# gamebuino-hack.net
KiCad netlist of a schematic drawn in EAGLE
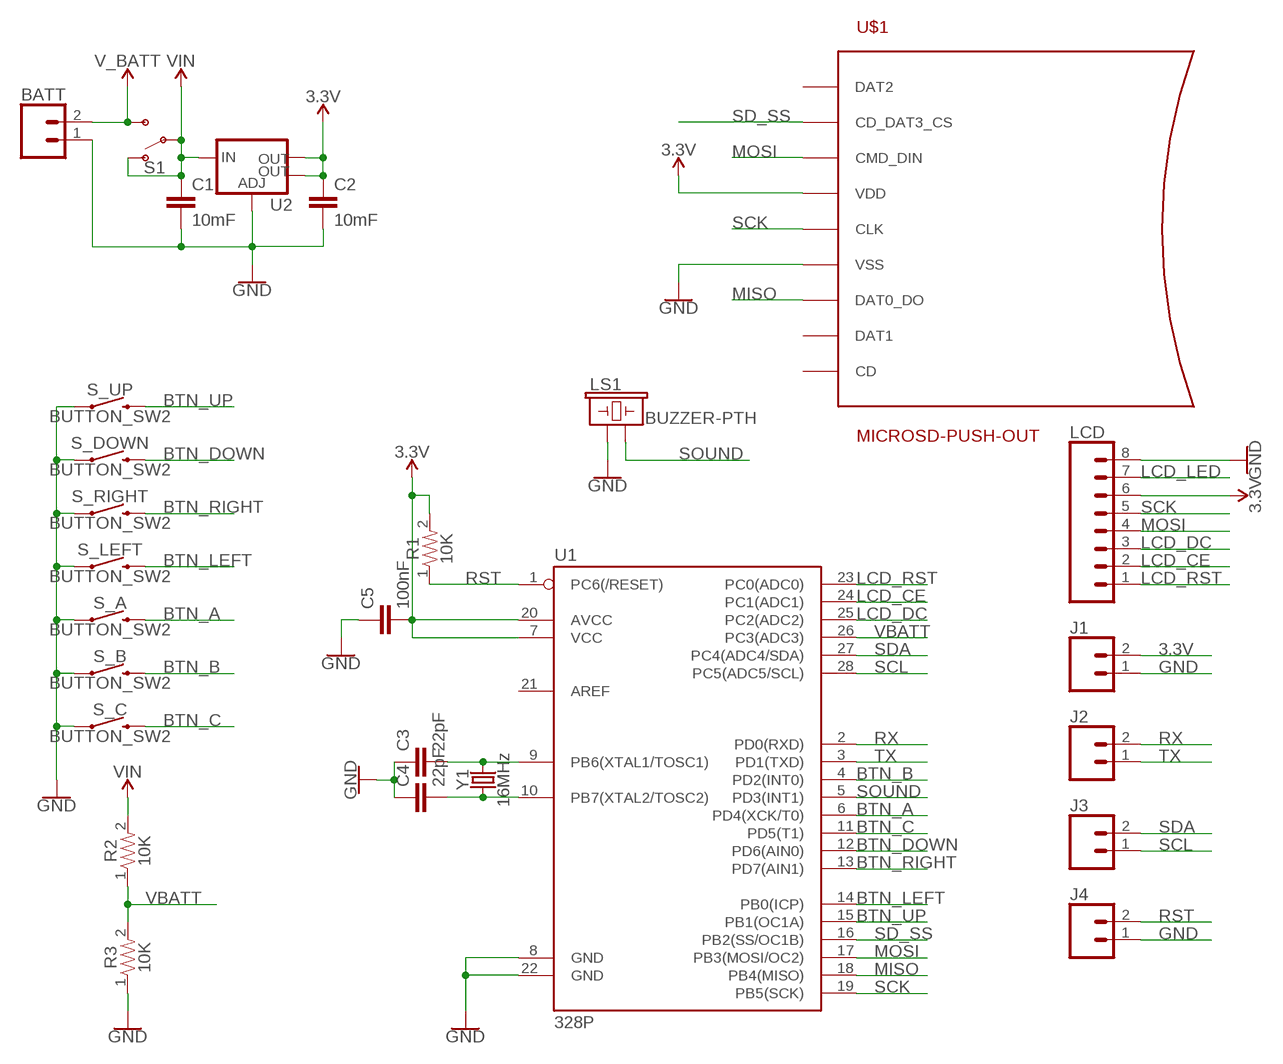
[diagram p0: schematic, sheet 1]

(export (version "E")
  (design (tool "Eeschema 10.0.6"))
  (components
    (comp (ref "BATT")
      (value "CONN_02")
      (footprint "eagle-import:1X02")
      (libsource (lib "eagle-import") (part "CONN_02"))
    )
    (comp (ref "C1")
      (value "10mF")
      (footprint "eagle-import:0805")
      (libsource (lib "eagle-import") (part "CAP-805"))
    )
    (comp (ref "C2")
      (value "10mF")
      (footprint "eagle-import:0805")
      (libsource (lib "eagle-import") (part "CAP-805"))
    )
    (comp (ref "C3")
      (value "22pF")
      (footprint "eagle-import:0805")
      (libsource (lib "eagle-import") (part "CAP-805"))
    )
    (comp (ref "C4")
      (value "22pF")
      (footprint "eagle-import:0805")
      (libsource (lib "eagle-import") (part "CAP-805"))
    )
    (comp (ref "C5")
      (value "100nF")
      (footprint "eagle-import:0805")
      (libsource (lib "eagle-import") (part "CAP-805"))
    )
    (comp (ref "J1")
      (value "CONN_02")
      (footprint "eagle-import:1X02")
      (libsource (lib "eagle-import") (part "CONN_02"))
    )
    (comp (ref "J2")
      (value "CONN_02")
      (footprint "eagle-import:1X02")
      (libsource (lib "eagle-import") (part "CONN_02"))
    )
    (comp (ref "J3")
      (value "CONN_02")
      (footprint "eagle-import:1X02")
      (libsource (lib "eagle-import") (part "CONN_02"))
    )
    (comp (ref "J4")
      (value "CONN_02")
      (footprint "eagle-import:1X02")
      (libsource (lib "eagle-import") (part "CONN_02"))
    )
    (comp (ref "LCD")
      (value "CONN_08\"")
      (footprint "eagle-import:1X08")
      (libsource (lib "eagle-import") (part "CONN_08{dblquote}"))
    )
    (comp (ref "LS1")
      (value "BUZZER-PTH")
      (footprint "eagle-import:BUZZER-12MM")
      (libsource (lib "eagle-import") (part "BUZZER-PTH"))
    )
    (comp (ref "R1")
      (value "10K")
      (footprint "eagle-import:0805")
      (libsource (lib "eagle-import") (part "RESISTOR-805"))
    )
    (comp (ref "R2")
      (value "10K")
      (footprint "eagle-import:0805")
      (libsource (lib "eagle-import") (part "RESISTOR-805"))
    )
    (comp (ref "R3")
      (value "10K")
      (footprint "eagle-import:0805")
      (libsource (lib "eagle-import") (part "RESISTOR-805"))
    )
    (comp (ref "S1")
      (value "SWITCH-SPDT-PTH-11.6X4.0MM")
      (footprint "eagle-import:SWITCH_SPDT_PTH_11.6X4.0MM")
      (libsource (lib "eagle-import") (part "SWITCH-SPDT-PTH-11.6X4.0MM"))
    )
    (comp (ref "S_A")
      (value "BUTTON_SW2")
      (footprint "eagle-import:BUTTON_SW2")
      (libsource (lib "eagle-import") (part "BUTTON_SW2"))
    )
    (comp (ref "S_B")
      (value "BUTTON_SW2")
      (footprint "eagle-import:BUTTON_SW2")
      (libsource (lib "eagle-import") (part "BUTTON_SW2"))
    )
    (comp (ref "S_C")
      (value "BUTTON_SW2")
      (footprint "eagle-import:BUTTON_SW2")
      (libsource (lib "eagle-import") (part "BUTTON_SW2"))
    )
    (comp (ref "S_DOWN")
      (value "BUTTON_SW2")
      (footprint "eagle-import:BUTTON_SW2")
      (libsource (lib "eagle-import") (part "BUTTON_SW2"))
    )
    (comp (ref "S_LEFT")
      (value "BUTTON_SW2")
      (footprint "eagle-import:BUTTON_SW2")
      (libsource (lib "eagle-import") (part "BUTTON_SW2"))
    )
    (comp (ref "S_RIGHT")
      (value "BUTTON_SW2")
      (footprint "eagle-import:BUTTON_SW2")
      (libsource (lib "eagle-import") (part "BUTTON_SW2"))
    )
    (comp (ref "S_UP")
      (value "BUTTON_SW2")
      (footprint "eagle-import:BUTTON_SW2")
      (libsource (lib "eagle-import") (part "BUTTON_SW2"))
    )
    (comp (ref "U$1")
      (value "MICROSD-PUSH-OUT")
      (footprint "eagle-import:MICROSD-PUSH-OUT")
      (libsource (lib "eagle-import") (part "MICROSD-PUSH-OUT"))
    )
    (comp (ref "U1")
      (value "328P")
      (footprint "eagle-import:DIP28")
      (libsource (lib "eagle-import") (part "ATMEGA328P_PDIP"))
    )
    (comp (ref "U2")
      (value "V_REG_LM1117SOT223")
      (footprint "eagle-import:SOT223")
      (libsource (lib "eagle-import") (part "V_REG_LM1117SOT223"))
    )
    (comp (ref "Y1")
      (value "16MHz")
      (footprint "eagle-import:HC49US")
      (libsource (lib "eagle-import") (part "CRYSTAL-16MHZPTH-HC49US"))
    )
  )
  (nets
    (net (code "1") (name "/BTN_A") (class "Default")
      (node (ref "S_A") (pin "2") (pinfunction "2_2") (pintype "passive"))
      (node (ref "U1") (pin "6") (pinfunction "PD4(XCK/T0)_6") (pintype "bidirectional"))
    )
    (net (code "2") (name "/BTN_B") (class "Default")
      (node (ref "S_B") (pin "2") (pinfunction "2_2") (pintype "passive"))
      (node (ref "U1") (pin "4") (pinfunction "PD2(INT0)_4") (pintype "bidirectional"))
    )
    (net (code "3") (name "/BTN_C") (class "Default")
      (node (ref "S_C") (pin "2") (pinfunction "2_2") (pintype "passive"))
      (node (ref "U1") (pin "11") (pinfunction "PD5(T1)_11") (pintype "bidirectional"))
    )
    (net (code "4") (name "/BTN_DOWN") (class "Default")
      (node (ref "S_DOWN") (pin "2") (pinfunction "2_2") (pintype "passive"))
      (node (ref "U1") (pin "12") (pinfunction "PD6(AIN0)_12") (pintype "bidirectional"))
    )
    (net (code "5") (name "/BTN_LEFT") (class "Default")
      (node (ref "S_LEFT") (pin "2") (pinfunction "2_2") (pintype "passive"))
      (node (ref "U1") (pin "14") (pinfunction "PB0(ICP)_14") (pintype "bidirectional"))
    )
    (net (code "6") (name "/BTN_RIGHT") (class "Default")
      (node (ref "S_RIGHT") (pin "2") (pinfunction "2_2") (pintype "passive"))
      (node (ref "U1") (pin "13") (pinfunction "PD7(AIN1)_13") (pintype "bidirectional"))
    )
    (net (code "7") (name "/BTN_UP") (class "Default")
      (node (ref "S_UP") (pin "2") (pinfunction "2_2") (pintype "passive"))
      (node (ref "U1") (pin "15") (pinfunction "PB1(OC1A)_15") (pintype "bidirectional"))
    )
    (net (code "8") (name "/LCD_CE") (class "Default")
      (node (ref "LCD") (pin "2") (pinfunction "2_2") (pintype "passive"))
      (node (ref "U1") (pin "24") (pinfunction "PC1(ADC1)_24") (pintype "bidirectional"))
    )
    (net (code "9") (name "/LCD_DC") (class "Default")
      (node (ref "LCD") (pin "3") (pinfunction "3_3") (pintype "passive"))
      (node (ref "U1") (pin "25") (pinfunction "PC2(ADC2)_25") (pintype "bidirectional"))
    )
    (net (code "10") (name "/LCD_LED") (class "Default")
      (node (ref "LCD") (pin "7") (pinfunction "7_7") (pintype "passive"))
    )
    (net (code "11") (name "/LCD_RST") (class "Default")
      (node (ref "LCD") (pin "1") (pinfunction "1_1") (pintype "passive"))
      (node (ref "U1") (pin "23") (pinfunction "PC0(ADC0)_23") (pintype "bidirectional"))
    )
    (net (code "12") (name "/MISO") (class "Default")
      (node (ref "U$1") (pin "7") (pinfunction "DAT0_DO_7") (pintype "bidirectional"))
      (node (ref "U1") (pin "18") (pinfunction "PB4(MISO)_18") (pintype "bidirectional"))
    )
    (net (code "13") (name "/MOSI") (class "Default")
      (node (ref "LCD") (pin "4") (pinfunction "4_4") (pintype "passive"))
      (node (ref "U$1") (pin "3") (pinfunction "CMD_DIN_3") (pintype "bidirectional"))
      (node (ref "U1") (pin "17") (pinfunction "PB3(MOSI/OC2)_17") (pintype "bidirectional"))
    )
    (net (code "14") (name "/RST") (class "Default")
      (node (ref "J4") (pin "2") (pinfunction "2_2") (pintype "passive"))
      (node (ref "R1") (pin "1") (pinfunction "1_1") (pintype "passive"))
      (node (ref "U1") (pin "1") (pinfunction "PC6(/RESET)_1") (pintype "bidirectional"))
    )
    (net (code "15") (name "/RX") (class "Default")
      (node (ref "J2") (pin "2") (pinfunction "2_2") (pintype "passive"))
      (node (ref "U1") (pin "2") (pinfunction "PD0(RXD)_2") (pintype "bidirectional"))
    )
    (net (code "16") (name "/SCK") (class "Default")
      (node (ref "LCD") (pin "5") (pinfunction "5_5") (pintype "passive"))
      (node (ref "U$1") (pin "5") (pinfunction "CLK_5") (pintype "bidirectional"))
      (node (ref "U1") (pin "19") (pinfunction "PB5(SCK)_19") (pintype "bidirectional"))
    )
    (net (code "17") (name "/SCL") (class "Default")
      (node (ref "J3") (pin "1") (pinfunction "1_1") (pintype "passive"))
      (node (ref "U1") (pin "28") (pinfunction "PC5(ADC5/SCL)_28") (pintype "bidirectional"))
    )
    (net (code "18") (name "/SDA") (class "Default")
      (node (ref "J3") (pin "2") (pinfunction "2_2") (pintype "passive"))
      (node (ref "U1") (pin "27") (pinfunction "PC4(ADC4/SDA)_27") (pintype "bidirectional"))
    )
    (net (code "19") (name "/SD_SS") (class "Default")
      (node (ref "U$1") (pin "2") (pinfunction "CD_DAT3_CS_2") (pintype "bidirectional"))
      (node (ref "U1") (pin "16") (pinfunction "PB2(SS/OC1B)_16") (pintype "bidirectional"))
    )
    (net (code "20") (name "/SOUND") (class "Default")
      (node (ref "LS1") (pin "-") (pinfunction "2_-") (pintype "passive"))
      (node (ref "U1") (pin "5") (pinfunction "PD3(INT1)_5") (pintype "bidirectional"))
    )
    (net (code "21") (name "/TX") (class "Default")
      (node (ref "J2") (pin "1") (pinfunction "1_1") (pintype "passive"))
      (node (ref "U1") (pin "3") (pinfunction "PD1(TXD)_3") (pintype "bidirectional"))
    )
    (net (code "22") (name "/VBATT") (class "Default")
      (node (ref "R2") (pin "1") (pinfunction "1_1") (pintype "passive"))
      (node (ref "R3") (pin "2") (pinfunction "2_2") (pintype "passive"))
      (node (ref "U1") (pin "26") (pinfunction "PC3(ADC3)_26") (pintype "bidirectional"))
    )
    (net (code "23") (name "3.3V") (class "Default")
      (node (ref "C2") (pin "1") (pinfunction "1_1") (pintype "passive"))
      (node (ref "C5") (pin "2") (pinfunction "2_2") (pintype "passive"))
      (node (ref "J1") (pin "2") (pinfunction "2_2") (pintype "passive"))
      (node (ref "LCD") (pin "6") (pinfunction "6_6") (pintype "passive"))
      (node (ref "R1") (pin "2") (pinfunction "2_2") (pintype "passive"))
      (node (ref "U$1") (pin "4") (pinfunction "VDD_4") (pintype "bidirectional"))
      (node (ref "U1") (pin "20") (pinfunction "AVCC_20") (pintype "bidirectional"))
      (node (ref "U1") (pin "7") (pinfunction "VCC_7") (pintype "bidirectional"))
      (node (ref "U2") (pin "2") (pinfunction "OUT_2") (pintype "output"))
      (node (ref "U2") (pin "4") (pinfunction "OUT_4") (pintype "output"))
    )
    (net (code "24") (name "GND") (class "Default")
      (node (ref "BATT") (pin "1") (pinfunction "1_1") (pintype "passive"))
      (node (ref "C1") (pin "2") (pinfunction "2_2") (pintype "passive"))
      (node (ref "C2") (pin "2") (pinfunction "2_2") (pintype "passive"))
      (node (ref "C3") (pin "1") (pinfunction "1_1") (pintype "passive"))
      (node (ref "C4") (pin "1") (pinfunction "1_1") (pintype "passive"))
      (node (ref "C5") (pin "1") (pinfunction "1_1") (pintype "passive"))
      (node (ref "J1") (pin "1") (pinfunction "1_1") (pintype "passive"))
      (node (ref "J4") (pin "1") (pinfunction "1_1") (pintype "passive"))
      (node (ref "LCD") (pin "8") (pinfunction "8_8") (pintype "passive"))
      (node (ref "LS1") (pin "+") (pinfunction "1_+") (pintype "passive"))
      (node (ref "R3") (pin "1") (pinfunction "1_1") (pintype "passive"))
      (node (ref "S_A") (pin "1") (pinfunction "1_1") (pintype "passive"))
      (node (ref "S_B") (pin "1") (pinfunction "1_1") (pintype "passive"))
      (node (ref "S_C") (pin "1") (pinfunction "1_1") (pintype "passive"))
      (node (ref "S_DOWN") (pin "1") (pinfunction "1_1") (pintype "passive"))
      (node (ref "S_LEFT") (pin "1") (pinfunction "1_1") (pintype "passive"))
      (node (ref "S_RIGHT") (pin "1") (pinfunction "1_1") (pintype "passive"))
      (node (ref "S_UP") (pin "1") (pinfunction "1_1") (pintype "passive"))
      (node (ref "U$1") (pin "6") (pinfunction "VSS_6") (pintype "bidirectional"))
      (node (ref "U$1") (pin "G1") (pinfunction "VSS_G1") (pintype "bidirectional"))
      (node (ref "U$1") (pin "G2") (pinfunction "VSS_G2") (pintype "bidirectional"))
      (node (ref "U$1") (pin "G3") (pinfunction "VSS_G3") (pintype "bidirectional"))
      (node (ref "U$1") (pin "G4") (pinfunction "VSS_G4") (pintype "bidirectional"))
      (node (ref "U1") (pin "22") (pinfunction "GND_22") (pintype "bidirectional"))
      (node (ref "U1") (pin "8") (pinfunction "GND_8") (pintype "bidirectional"))
      (node (ref "U2") (pin "1") (pinfunction "ADJ_1") (pintype "input"))
    )
    (net (code "25") (name "Net-(U1-PB6(XTAL1{slash}TOSC1))") (class "Default")
      (node (ref "C3") (pin "2") (pinfunction "2_2") (pintype "passive"))
      (node (ref "U1") (pin "9") (pinfunction "PB6(XTAL1/TOSC1)_9") (pintype "bidirectional"))
      (node (ref "Y1") (pin "2") (pinfunction "2_2") (pintype "passive"))
    )
    (net (code "26") (name "Net-(U1-PB7(XTAL2{slash}TOSC2))") (class "Default")
      (node (ref "C4") (pin "2") (pinfunction "2_2") (pintype "passive"))
      (node (ref "U1") (pin "10") (pinfunction "PB7(XTAL2/TOSC2)_10") (pintype "bidirectional"))
      (node (ref "Y1") (pin "1") (pinfunction "1_1") (pintype "passive"))
    )
    (net (code "27") (name "VIN") (class "Default")
      (node (ref "C1") (pin "1") (pinfunction "1_1") (pintype "passive"))
      (node (ref "R2") (pin "2") (pinfunction "2_2") (pintype "passive"))
      (node (ref "S1") (pin "1") (pinfunction "O_1") (pintype "passive"))
      (node (ref "S1") (pin "2") (pinfunction "P_2") (pintype "passive"))
      (node (ref "U2") (pin "3") (pinfunction "IN_3") (pintype "input"))
    )
    (net (code "28") (name "V_BATT") (class "Default")
      (node (ref "BATT") (pin "2") (pinfunction "2_2") (pintype "passive"))
      (node (ref "S1") (pin "3") (pinfunction "S_3") (pintype "passive"))
    )
    (net (code "29") (name "unconnected-(U$1-DAT1-Pad8)") (class "Default")
      (node (ref "U$1") (pin "8") (pinfunction "DAT1_8") (pintype "bidirectional"))
    )
    (net (code "30") (name "unconnected-(U$1-DAT2-Pad1)") (class "Default")
      (node (ref "U$1") (pin "1") (pinfunction "DAT2_1") (pintype "bidirectional"))
    )
    (net (code "31") (name "unconnected-(U$1-PadCD)") (class "Default")
      (node (ref "U$1") (pin "CD") (pinfunction "CD_CD") (pintype "bidirectional"))
    )
    (net (code "32") (name "unconnected-(U1-AREF-Pad21)") (class "Default")
      (node (ref "U1") (pin "21") (pinfunction "AREF_21") (pintype "bidirectional"))
    )
  )
)
